# DDS.net
KiCad netlist of a schematic drawn in Altium Designer
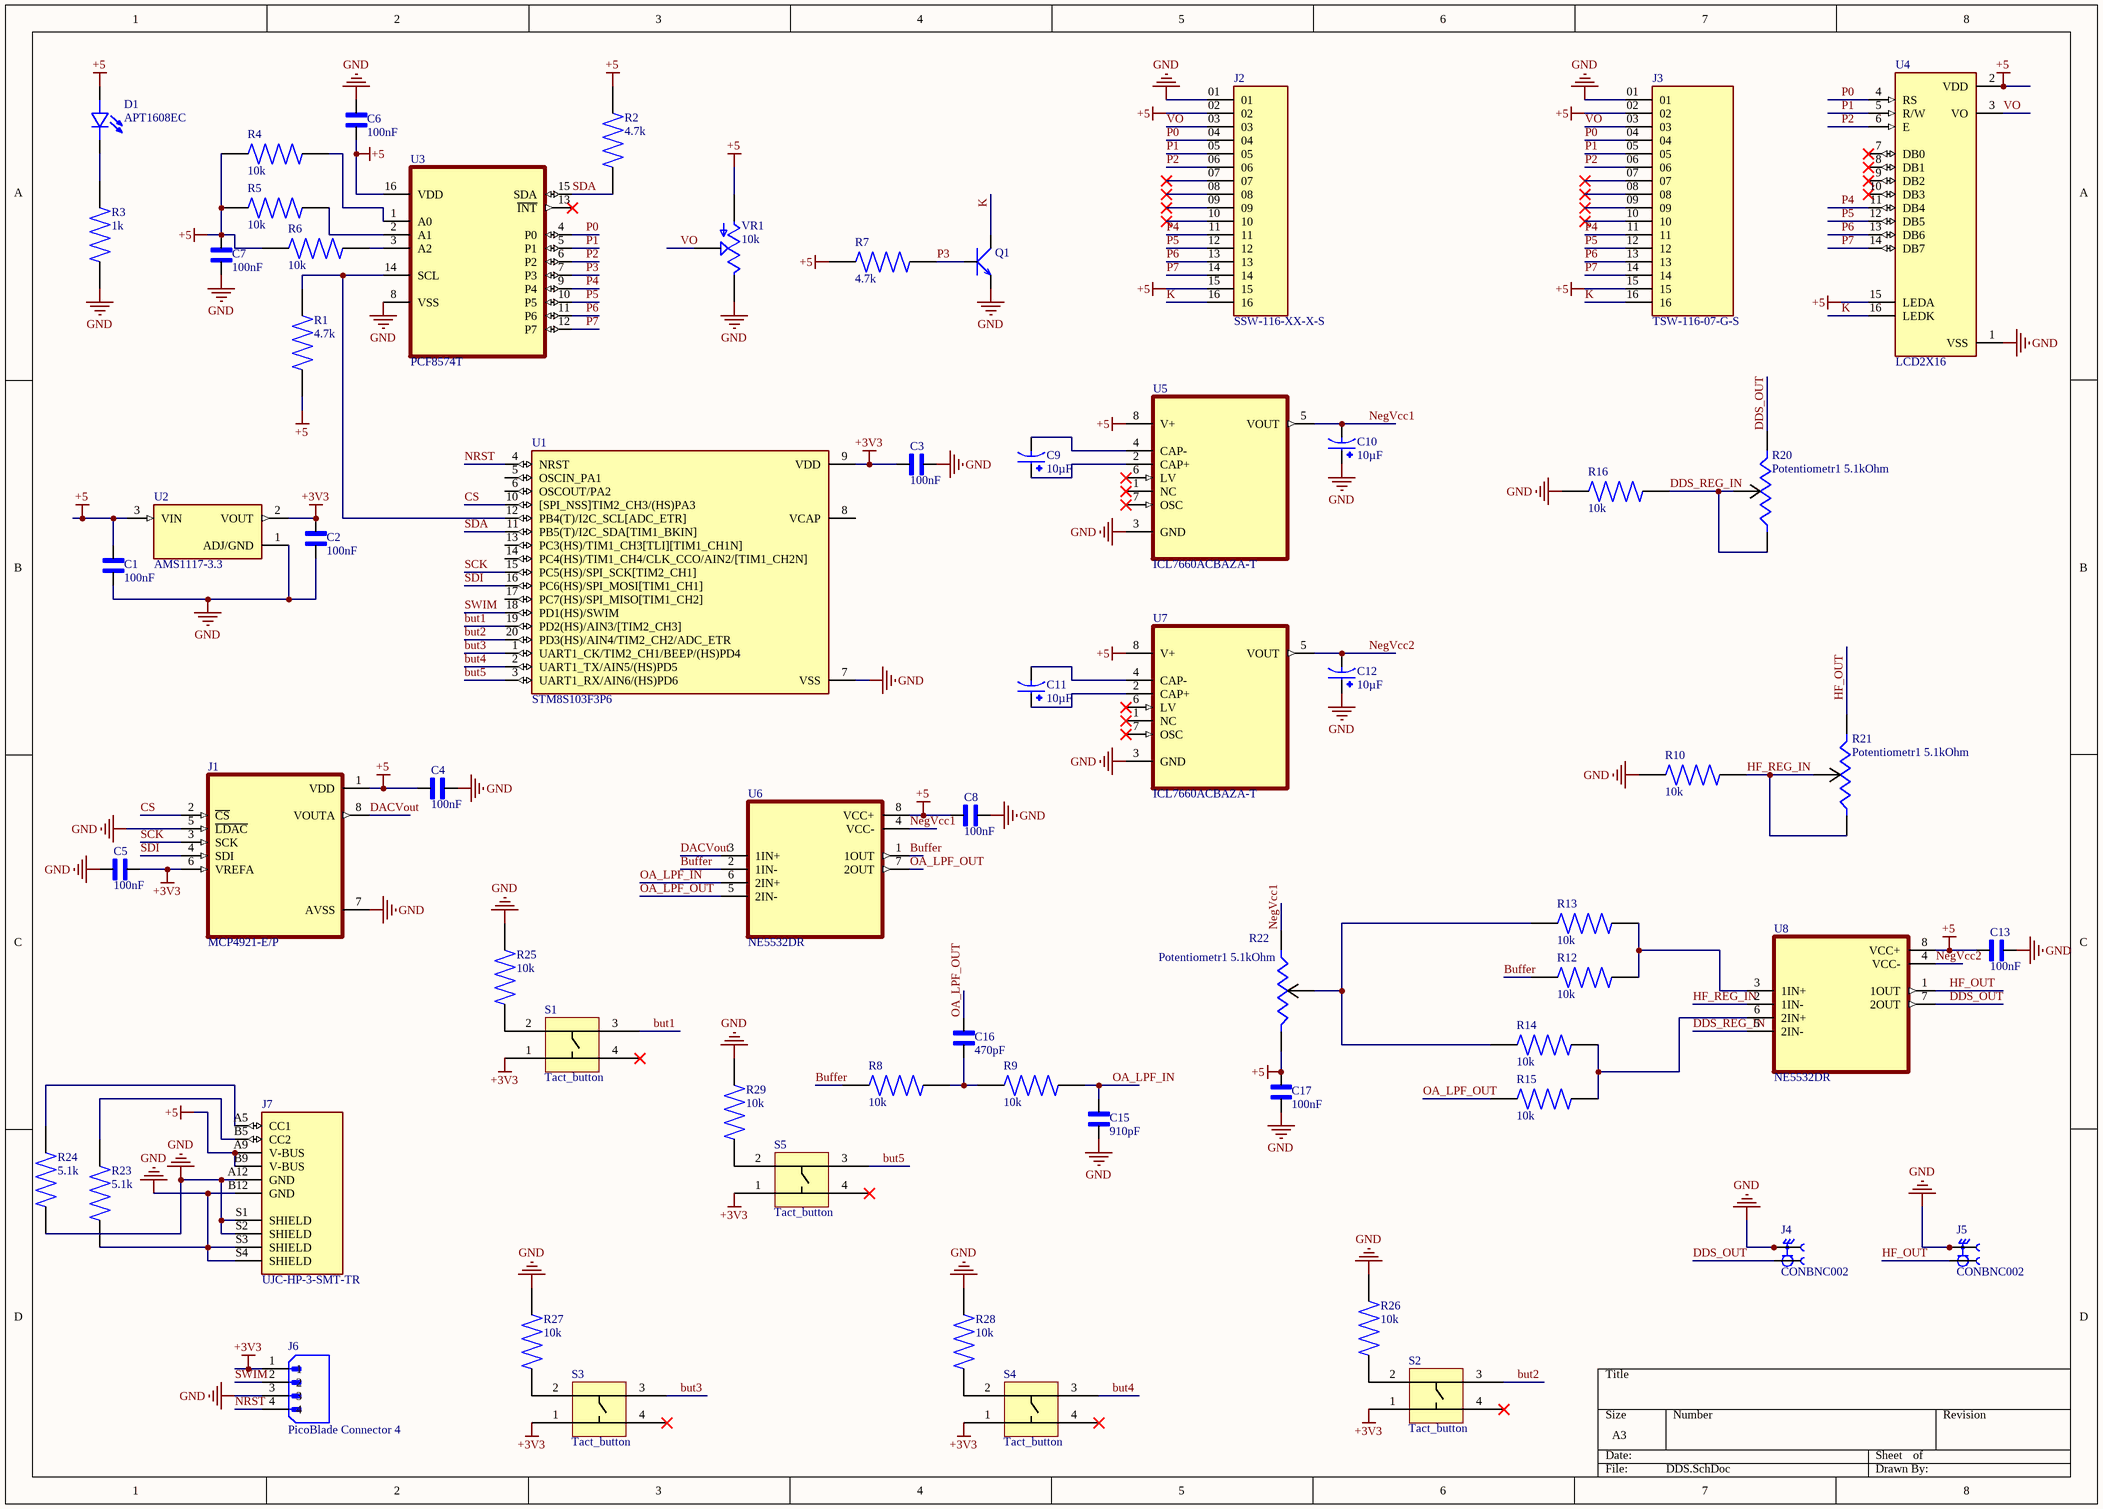
[diagram p0: DDS.SchDoc]

(export (version "E")
  (design (tool "Eeschema 10.0.6"))
  (components
    (comp (ref "C1")
      (value "100nF")
      (footprint "CAPC1608X90N")
      (description "0.1 ВµF В±10% 50V Ceramic Capacitor X7R 0603 (1608 Metric)")
      (fields (field (name "MF") "Samsung Electro-Mechanics") (field (name "MP") "CL10B104KB8NNNC"))
      (libsource (lib "") (part "CL10B104KB8NNNC_2"))
    )
    (comp (ref "C2")
      (value "100nF")
      (footprint "CAPC1608X90N")
      (description "0.1 ВµF В±10% 50V Ceramic Capacitor X7R 0603 (1608 Metric)")
      (fields (field (name "MF") "Samsung Electro-Mechanics") (field (name "MP") "CL10B104KB8NNNC"))
      (libsource (lib "") (part "CL10B104KB8NNNC_2"))
    )
    (comp (ref "C3")
      (value "100nF")
      (footprint "CAPC1608X90N")
      (description "0.1 ВµF В±10% 50V Ceramic Capacitor X7R 0603 (1608 Metric)")
      (fields (field (name "MF") "Samsung Electro-Mechanics") (field (name "MP") "CL10B104KB8NNNC"))
      (libsource (lib "") (part "CL10B104KB8NNNC_1"))
    )
    (comp (ref "C4")
      (value "100nF")
      (footprint "CAPC1608X90N")
      (description "0.1 ВµF В±10% 50V Ceramic Capacitor X7R 0603 (1608 Metric)")
      (fields (field (name "MF") "Samsung Electro-Mechanics") (field (name "MP") "CL10B104KB8NNNC"))
      (libsource (lib "") (part "CL10B104KB8NNNC_1"))
    )
    (comp (ref "C5")
      (value "100nF")
      (footprint "CAPC1608X90N")
      (description "0.1 ВµF В±10% 50V Ceramic Capacitor X7R 0603 (1608 Metric)")
      (fields (field (name "MF") "Samsung Electro-Mechanics") (field (name "MP") "CL10B104KB8NNNC"))
      (libsource (lib "National Technical University of Ukraine Igor Sikorsky Kyiv Polytechnic Institute- Educator Program") (part "CL10B104KB8NNNC"))
    )
    (comp (ref "C6")
      (value "100nF")
      (footprint "CAPC1608X90N")
      (description "0.1 ВµF В±10% 50V Ceramic Capacitor X7R 0603 (1608 Metric)")
      (fields (field (name "MF") "Samsung Electro-Mechanics") (field (name "MP") "CL10B104KB8NNNC"))
      (libsource (lib "") (part "CL10B104KB8NNNC_3"))
    )
    (comp (ref "C7")
      (value "100nF")
      (footprint "CAPC1608X90N")
      (description "0.1 ВµF В±10% 50V Ceramic Capacitor X7R 0603 (1608 Metric)")
      (fields (field (name "MF") "Samsung Electro-Mechanics") (field (name "MP") "CL10B104KB8NNNC"))
      (libsource (lib "") (part "CL10B104KB8NNNC_2"))
    )
    (comp (ref "C8")
      (value "100nF")
      (footprint "CAPC1608X90N")
      (description "0.1 ВµF В±10% 50V Ceramic Capacitor X7R 0603 (1608 Metric)")
      (fields (field (name "MF") "Samsung Electro-Mechanics") (field (name "MP") "CL10B104KB8NNNC"))
      (libsource (lib "") (part "CL10B104KB8NNNC_1"))
    )
    (comp (ref "C9")
      (value "10µF")
      (footprint "CAPPRD150W45D400H700")
      (description "10F 25V Aluminum Electrolytic Capacitors Radial, Can 1000 Hrs @ 105C")
      (fields (field (name "MP") "EEAFC1E100") (field (name "MF") "Panasonic"))
      (libsource (lib "National Technical University of Ukraine Igor Sikorsky Kyiv Polytechnic Institute- Educator Program") (part "EEAFC1E100"))
    )
    (comp (ref "C10")
      (value "10µF")
      (footprint "CAPPRD150W45D400H700")
      (description "10F 25V Aluminum Electrolytic Capacitors Radial, Can 1000 Hrs @ 105C")
      (fields (field (name "MP") "EEAFC1E100") (field (name "MF") "Panasonic"))
      (libsource (lib "National Technical University of Ukraine Igor Sikorsky Kyiv Polytechnic Institute- Educator Program") (part "EEAFC1E100"))
    )
    (comp (ref "C11")
      (value "10µF")
      (footprint "CAPPRD150W45D400H700")
      (description "10F 25V Aluminum Electrolytic Capacitors Radial, Can 1000 Hrs @ 105C")
      (fields (field (name "MP") "EEAFC1E100") (field (name "MF") "Panasonic"))
      (libsource (lib "National Technical University of Ukraine Igor Sikorsky Kyiv Polytechnic Institute- Educator Program") (part "EEAFC1E100"))
    )
    (comp (ref "C12")
      (value "10µF")
      (footprint "CAPPRD150W45D400H700")
      (description "10F 25V Aluminum Electrolytic Capacitors Radial, Can 1000 Hrs @ 105C")
      (fields (field (name "MP") "EEAFC1E100") (field (name "MF") "Panasonic"))
      (libsource (lib "National Technical University of Ukraine Igor Sikorsky Kyiv Polytechnic Institute- Educator Program") (part "EEAFC1E100"))
    )
    (comp (ref "C13")
      (value "100nF")
      (footprint "CAPC1608X90N")
      (description "0.1 ВµF В±10% 50V Ceramic Capacitor X7R 0603 (1608 Metric)")
      (fields (field (name "MF") "Samsung Electro-Mechanics") (field (name "MP") "CL10B104KB8NNNC"))
      (libsource (lib "") (part "CL10B104KB8NNNC_1"))
    )
    (comp (ref "C15")
      (value "910pF")
      (footprint "CAPC0603X33N")
      (fields (field (name "MF") "Murata") (field (name "MP") "GRM0335C1E911JA01D"))
      (libsource (lib "National Technical University of Ukraine Igor Sikorsky Kyiv Polytechnic Institute- Educator Program") (part "GRM0335C1E911JA01D"))
    )
    (comp (ref "C16")
      (value "470pF")
      (footprint "CAPC1608X90N")
      (description "470 pF В±5% 50V Ceramic Capacitor C0G, NP0 0603 (1608 Metric)")
      (fields (field (name "MF") "Samsung") (field (name "MP") "CL10C471JB8NNNC"))
      (libsource (lib "National Technical University of Ukraine Igor Sikorsky Kyiv Polytechnic Institute- Educator Program") (part "CL10C471JB8NNNC"))
    )
    (comp (ref "C17")
      (value "100nF")
      (footprint "CAPC1608X90N")
      (description "0.1 ВµF В±10% 50V Ceramic Capacitor X7R 0603 (1608 Metric)")
      (fields (field (name "MF") "Samsung Electro-Mechanics") (field (name "MP") "CL10B104KB8NNNC"))
      (libsource (lib "") (part "CL10B104KB8NNNC_2"))
    )
    (comp (ref "D1")
      (value "APT1608EC")
      (footprint "LED_APT1608EC")
      (description "Red 617nm LED Indication - Discrete 2V 0603 (1608 Metric)")
      (fields (field (name "MF") "Kingbright"))
      (libsource (lib "National Technical University of Ukraine Igor Sikorsky Kyiv Polytechnic Institute- Educator Program") (part "APT1608EC"))
    )
    (comp (ref "J1")
      (value "MCP4921-E/P")
      (footprint "DIP787W46P254L927H533Q8")
      (description "Microchip 12 bit Serial DAC 8-Pin PDIP")
      (fields (field (name "MF") "Microchip"))
      (libsource (lib "National Technical University of Ukraine Igor Sikorsky Kyiv Polytechnic Institute- Educator Program") (part "MCP4921-E/P"))
    )
    (comp (ref "J2")
      (value "SSW-116-XX-X-S")
      (footprint "SAMTEC_SSW-116-XX-X-S")
      (description "Conn Socket Strip SKT 16 POS 2.54mm Solder ST Top Entry Thru-Hole Bulk")
      (fields (field (name "MP") "SSW-116-06-G-S") (field (name "MF") "Samtec"))
      (libsource (lib "National Technical University of Ukraine Igor Sikorsky Kyiv Polytechnic Institute- Educator Program") (part "SSW-116-XX-X-S"))
    )
    (comp (ref "J3")
      (value "TSW-116-07-G-S")
      (footprint "SAMTEC_TSW-116-07-G-S")
      (fields (field (name "MF") "Samtec"))
      (libsource (lib "National Technical University of Ukraine Igor Sikorsky Kyiv Polytechnic Institute- Educator Program") (part "TSW-116-07-G-S"))
    )
    (comp (ref "J4")
      (value "CONBNC002")
      (footprint "LINX_CONBNC002")
      (description "BNC Jack 50 Ohm PCB Through Hole")
      (fields (field (name "MF") "Linx Technologies Inc."))
      (libsource (lib "National Technical University of Ukraine Igor Sikorsky Kyiv Polytechnic Institute- Educator Program") (part "CONBNC002"))
    )
    (comp (ref "J5")
      (value "CONBNC002")
      (footprint "LINX_CONBNC002")
      (description "BNC Jack 50 Ohm PCB Through Hole")
      (fields (field (name "MF") "Linx Technologies Inc."))
      (libsource (lib "National Technical University of Ukraine Igor Sikorsky Kyiv Polytechnic Institute- Educator Program") (part "CONBNC002"))
    )
    (comp (ref "J6")
      (value "PicoBlade Connector 4")
      (footprint "MOLEX_530470410")
      (description "Connector Header Through Hole 4 position 0.049 (1.25mm)")
      (fields (field (name "MF") "Molex") (field (name "MP") "530470410"))
      (libsource (lib "National Technical University of Ukraine Igor Sikorsky Kyiv Polytechnic Institute- Educator Program") (part "530470410"))
    )
    (comp (ref "J7")
      (value "UJC-HP-3-SMT-TR")
      (footprint "CUI_UJC-HP-3-SMT-TR")
      (libsource (lib "National Technical University of Ukraine Igor Sikorsky Kyiv Polytechnic Institute- Educator Program") (part "UJC-HP-3-SMT-TR"))
    )
    (comp (ref "Q1")
      (value "SMD-TRANSISTORS-NPN-25V-500MW(SOT-23)")
      (footprint "SOT-23")
      (description "Bipolar (BJT) Transistor NPN 25 V 500 mA 150MHz 300 mW Surface Mount SOT-23")
      (fields (field (name "MF") "UMW") (field (name "MP") "S8050"))
      (libsource (lib "National Technical University of Ukraine Igor Sikorsky Kyiv Polytechnic Institute- Educator Program") (part "SMD-TRANSISTORS-NPN-25V-500MW(SOT-23)"))
    )
    (comp (ref "R1")
      (value "4.7k")
      (footprint "RESC1608X55N")
      (description "Res Thick Film 0603 4.7K Ohm 1% 0.2W(1/5W) В±200ppm/C Pad SMD Automotive T/R")
      (fields (field (name "MF") "Panasonic") (field (name "MP") "ERJ-P03F4701V"))
      (libsource (lib "National Technical University of Ukraine Igor Sikorsky Kyiv Polytechnic Institute- Educator Program") (part "ERJ-P03F4701V"))
    )
    (comp (ref "R2")
      (value "4.7k")
      (footprint "RESC1608X55N")
      (description "Res Thick Film 0603 4.7K Ohm 1% 0.2W(1/5W) В±200ppm/C Pad SMD Automotive T/R")
      (fields (field (name "MF") "Panasonic") (field (name "MP") "ERJ-P03F4701V"))
      (libsource (lib "National Technical University of Ukraine Igor Sikorsky Kyiv Polytechnic Institute- Educator Program") (part "ERJ-P03F4701V"))
    )
    (comp (ref "R3")
      (value "1k")
      (footprint "RES_ERJP03F1001V")
      (description "Thick Film Smnt Resistor 0603 Case 1kOhm +/-1% 0.2W +/-200ppm/degC")
      (fields (field (name "MP") "ERJP03F1001V") (field (name "MF") "Panasonic"))
      (libsource (lib "National Technical University of Ukraine Igor Sikorsky Kyiv Polytechnic Institute- Educator Program") (part "ERJP03F1001V"))
    )
    (comp (ref "R4")
      (value "10k")
      (footprint "RES_ERJPA3F1002V")
      (fields
        (field (name "MP") "ERJ-PA3F1002V")
        (field (name "MF") "Panasonic")
        (field (name "Comment") "ERJPA3F1002V")
      )
      (libsource (lib "National Technical University of Ukraine Igor Sikorsky Kyiv Polytechnic Institute- Educator Program") (part "ERJPA3F1002V"))
    )
    (comp (ref "R5")
      (value "10k")
      (footprint "RES_ERJPA3F1002V")
      (fields
        (field (name "MP") "ERJ-PA3F1002V")
        (field (name "MF") "Panasonic")
        (field (name "Comment") "ERJPA3F1002V")
      )
      (libsource (lib "National Technical University of Ukraine Igor Sikorsky Kyiv Polytechnic Institute- Educator Program") (part "ERJPA3F1002V"))
    )
    (comp (ref "R6")
      (value "10k")
      (footprint "RES_ERJPA3F1002V")
      (fields
        (field (name "MP") "ERJ-PA3F1002V")
        (field (name "MF") "Panasonic")
        (field (name "Comment") "ERJPA3F1002V")
      )
      (libsource (lib "National Technical University of Ukraine Igor Sikorsky Kyiv Polytechnic Institute- Educator Program") (part "ERJPA3F1002V"))
    )
    (comp (ref "R7")
      (value "4.7k")
      (footprint "RESC1608X55N")
      (description "Res Thick Film 0603 4.7K Ohm 1% 0.2W(1/5W) В±200ppm/C Pad SMD Automotive T/R")
      (fields (field (name "MF") "Panasonic") (field (name "MP") "ERJ-P03F4701V"))
      (libsource (lib "National Technical University of Ukraine Igor Sikorsky Kyiv Polytechnic Institute- Educator Program") (part "ERJ-P03F4701V"))
    )
    (comp (ref "R8")
      (value "10k")
      (footprint "RES_ERJPA3F1002V")
      (fields
        (field (name "MP") "ERJ-PA3F1002V")
        (field (name "MF") "Panasonic")
        (field (name "Comment") "ERJPA3F1002V")
      )
      (libsource (lib "National Technical University of Ukraine Igor Sikorsky Kyiv Polytechnic Institute- Educator Program") (part "ERJPA3F1002V"))
    )
    (comp (ref "R9")
      (value "10k")
      (footprint "RES_ERJPA3F1002V")
      (fields
        (field (name "MP") "ERJ-PA3F1002V")
        (field (name "MF") "Panasonic")
        (field (name "Comment") "ERJPA3F1002V")
      )
      (libsource (lib "National Technical University of Ukraine Igor Sikorsky Kyiv Polytechnic Institute- Educator Program") (part "ERJPA3F1002V"))
    )
    (comp (ref "R10")
      (value "10k")
      (footprint "RES_ERJPA3F1002V")
      (fields
        (field (name "MP") "ERJ-PA3F1002V")
        (field (name "MF") "Panasonic")
        (field (name "Comment") "ERJPA3F1002V")
      )
      (libsource (lib "National Technical University of Ukraine Igor Sikorsky Kyiv Polytechnic Institute- Educator Program") (part "ERJPA3F1002V"))
    )
    (comp (ref "R12")
      (value "10k")
      (footprint "RES_ERJPA3F1002V")
      (fields
        (field (name "MP") "ERJ-PA3F1002V")
        (field (name "MF") "Panasonic")
        (field (name "Comment") "ERJPA3F1002V")
      )
      (libsource (lib "National Technical University of Ukraine Igor Sikorsky Kyiv Polytechnic Institute- Educator Program") (part "ERJPA3F1002V"))
    )
    (comp (ref "R13")
      (value "10k")
      (footprint "RES_ERJPA3F1002V")
      (fields
        (field (name "MP") "ERJ-PA3F1002V")
        (field (name "MF") "Panasonic")
        (field (name "Comment") "ERJPA3F1002V")
      )
      (libsource (lib "National Technical University of Ukraine Igor Sikorsky Kyiv Polytechnic Institute- Educator Program") (part "ERJPA3F1002V"))
    )
    (comp (ref "R14")
      (value "10k")
      (footprint "RES_ERJPA3F1002V")
      (fields
        (field (name "MP") "ERJ-PA3F1002V")
        (field (name "MF") "Panasonic")
        (field (name "Comment") "ERJPA3F1002V")
      )
      (libsource (lib "National Technical University of Ukraine Igor Sikorsky Kyiv Polytechnic Institute- Educator Program") (part "ERJPA3F1002V"))
    )
    (comp (ref "R15")
      (value "10k")
      (footprint "RES_ERJPA3F1002V")
      (fields
        (field (name "MP") "ERJ-PA3F1002V")
        (field (name "MF") "Panasonic")
        (field (name "Comment") "ERJPA3F1002V")
      )
      (libsource (lib "National Technical University of Ukraine Igor Sikorsky Kyiv Polytechnic Institute- Educator Program") (part "ERJPA3F1002V"))
    )
    (comp (ref "R16")
      (value "10k")
      (footprint "RES_ERJPA3F1002V")
      (fields
        (field (name "MP") "ERJ-PA3F1002V")
        (field (name "MF") "Panasonic")
        (field (name "Comment") "ERJPA3F1002V")
      )
      (libsource (lib "National Technical University of Ukraine Igor Sikorsky Kyiv Polytechnic Institute- Educator Program") (part "ERJPA3F1002V"))
    )
    (comp (ref "R20")
      (value "Potentiometr1 5.1kOhm")
      (footprint "PcbLib1:PotentiomenerFootprint")
      (libsource (lib "Schlib1") (part "Potentiometr1"))
    )
    (comp (ref "R21")
      (value "Potentiometr1 5.1kOhm")
      (footprint "PcbLib1:PotentiomenerFootprint")
      (libsource (lib "Schlib1") (part "Potentiometr1"))
    )
    (comp (ref "R22")
      (value "Potentiometr1 5.1kOhm")
      (footprint "PcbLib1:PotentiomenerFootprint")
      (libsource (lib "Schlib1") (part "Potentiometr1"))
    )
    (comp (ref "R23")
      (value "5.1k")
      (footprint "RES_ERJPA3F5101V")
      (description "Thick Film Smnt Resistor 0603 Case 5.1kOhm +/-1% 0.25W +/-100ppm/degC")
      (fields (field (name "MF") "Panasonic") (field (name "MP") "ERJPA3F5101V"))
      (libsource (lib "National Technical University of Ukraine Igor Sikorsky Kyiv Polytechnic Institute- Educator Program") (part "ERJPA3F5101V"))
    )
    (comp (ref "R24")
      (value "5.1k")
      (footprint "RES_ERJPA3F5101V")
      (description "Thick Film Smnt Resistor 0603 Case 5.1kOhm +/-1% 0.25W +/-100ppm/degC")
      (fields (field (name "MF") "Panasonic") (field (name "MP") "ERJPA3F5101V"))
      (libsource (lib "National Technical University of Ukraine Igor Sikorsky Kyiv Polytechnic Institute- Educator Program") (part "ERJPA3F5101V"))
    )
    (comp (ref "R25")
      (value "10k")
      (footprint "RES_ERJPA3F1002V")
      (fields
        (field (name "MP") "ERJ-PA3F1002V")
        (field (name "MF") "Panasonic")
        (field (name "Comment") "ERJPA3F1002V")
      )
      (libsource (lib "National Technical University of Ukraine Igor Sikorsky Kyiv Polytechnic Institute- Educator Program") (part "ERJPA3F1002V"))
    )
    (comp (ref "R26")
      (value "10k")
      (footprint "RES_ERJPA3F1002V")
      (fields
        (field (name "MP") "ERJ-PA3F1002V")
        (field (name "MF") "Panasonic")
        (field (name "Comment") "ERJPA3F1002V")
      )
      (libsource (lib "National Technical University of Ukraine Igor Sikorsky Kyiv Polytechnic Institute- Educator Program") (part "ERJPA3F1002V"))
    )
    (comp (ref "R27")
      (value "10k")
      (footprint "RES_ERJPA3F1002V")
      (fields
        (field (name "MP") "ERJ-PA3F1002V")
        (field (name "MF") "Panasonic")
        (field (name "Comment") "ERJPA3F1002V")
      )
      (libsource (lib "National Technical University of Ukraine Igor Sikorsky Kyiv Polytechnic Institute- Educator Program") (part "ERJPA3F1002V"))
    )
    (comp (ref "R28")
      (value "10k")
      (footprint "RES_ERJPA3F1002V")
      (fields
        (field (name "MP") "ERJ-PA3F1002V")
        (field (name "MF") "Panasonic")
        (field (name "Comment") "ERJPA3F1002V")
      )
      (libsource (lib "National Technical University of Ukraine Igor Sikorsky Kyiv Polytechnic Institute- Educator Program") (part "ERJPA3F1002V"))
    )
    (comp (ref "R29")
      (value "10k")
      (footprint "RES_ERJPA3F1002V")
      (fields
        (field (name "MP") "ERJ-PA3F1002V")
        (field (name "MF") "Panasonic")
        (field (name "Comment") "ERJPA3F1002V")
      )
      (libsource (lib "National Technical University of Ukraine Igor Sikorsky Kyiv Polytechnic Institute- Educator Program") (part "ERJPA3F1002V"))
    )
    (comp (ref "S1")
      (value "Tact_button")
      (footprint "TactButtonFootprint")
      (libsource (lib "Schlib1") (part "Tact_button"))
    )
    (comp (ref "S2")
      (value "Tact_button")
      (footprint "TactButtonFootprint")
      (libsource (lib "Schlib1") (part "Tact_button"))
    )
    (comp (ref "S3")
      (value "Tact_button")
      (footprint "TactButtonFootprint")
      (libsource (lib "Schlib1") (part "Tact_button"))
    )
    (comp (ref "S4")
      (value "Tact_button")
      (footprint "TactButtonFootprint")
      (libsource (lib "Schlib1") (part "Tact_button"))
    )
    (comp (ref "S5")
      (value "Tact_button")
      (footprint "TactButtonFootprint")
      (libsource (lib "Schlib1") (part "Tact_button"))
    )
    (comp (ref "U1")
      (value "STM8S103F3P6")
      (footprint "SOP65P640X120-20N")
      (description "STM8 series Microcontroller IC 8-Bit 16MHz 8KB (8K x 8) FLASH 20-TSSOP")
      (fields (field (name "MF") "STMicroelectronics"))
      (libsource (lib "National Technical University of Ukraine Igor Sikorsky Kyiv Polytechnic Institute- Educator Program") (part "STM8S103F3P6"))
    )
    (comp (ref "U2")
      (value "AMS1117-3.3")
      (footprint "SOT229P700X180-4N")
      (description "Linear Voltage Regulator IC Positive Fixed 1 Output 1A SOT-223-3L")
      (fields (field (name "MF") "UMW"))
      (libsource (lib "National Technical University of Ukraine Igor Sikorsky Kyiv Polytechnic Institute- Educator Program") (part "AMS1117-3.3"))
    )
    (comp (ref "U3")
      (value "PCF8574T")
      (footprint "SOIC127P1032X265-16N")
      (description "I/O Expander 8 IВІC 100 kHz 20-SSOP")
      (fields (field (name "MF") "NXP Semiconductors"))
      (libsource (lib "National Technical University of Ukraine Igor Sikorsky Kyiv Polytechnic Institute- Educator Program") (part "PCF8574T"))
    )
    (comp (ref "U4")
      (value "LCD2X16")
      (footprint "LCD_LCD2X16")
      (description "Display; Display: LCD 2x16 characters (blue backlight)")
      (fields (field (name "MF") "mikroElektronika") (field (name "MP") "LCD 2X16"))
      (libsource (lib "National Technical University of Ukraine Igor Sikorsky Kyiv Polytechnic Institute- Educator Program") (part "LCD2X16"))
    )
    (comp (ref "U5")
      (value "ICL7660ACBAZA-T")
      (footprint "SOIC127P600X175-8N")
      (fields (field (name "MF") "Renesas Electronics America Inc"))
      (libsource (lib "National Technical University of Ukraine Igor Sikorsky Kyiv Polytechnic Institute- Educator Program") (part "ICL7660ACBAZA-T"))
    )
    (comp (ref "U6")
      (value "NE5532DR")
      (footprint "SOIC127P599X175-8N")
      (description "Dual, 30-V, 10-MHz, low-noise operational amplifier for audio applications")
      (fields (field (name "MF") "Texas Instruments"))
      (libsource (lib "National Technical University of Ukraine Igor Sikorsky Kyiv Polytechnic Institute- Educator Program") (part "NE5532DR"))
    )
    (comp (ref "U7")
      (value "ICL7660ACBAZA-T")
      (footprint "SOIC127P600X175-8N")
      (fields (field (name "MF") "Renesas Electronics America Inc"))
      (libsource (lib "National Technical University of Ukraine Igor Sikorsky Kyiv Polytechnic Institute- Educator Program") (part "ICL7660ACBAZA-T"))
    )
    (comp (ref "U8")
      (value "NE5532DR")
      (footprint "SOIC127P599X175-8N")
      (description "Dual, 30-V, 10-MHz, low-noise operational amplifier for audio applications")
      (fields (field (name "MF") "Texas Instruments"))
      (libsource (lib "National Technical University of Ukraine Igor Sikorsky Kyiv Polytechnic Institute- Educator Program") (part "NE5532DR"))
    )
    (comp (ref "VR1")
      (value "10k")
      (footprint "TRIM_3362P-1-103LF")
      (description "Trimmer, Cermet, Rest 10 Kilohms, PCB, 1 Turns, Pwr-Rtg 0.5 W, Tol 10%")
      (fields (field (name "MP") "3362P-1-103LF") (field (name "MF") "Bourns"))
      (libsource (lib "National Technical University of Ukraine Igor Sikorsky Kyiv Polytechnic Institute- Educator Program") (part "3362P-1-103LF"))
    )
  )
  (nets
    (net (code "1") (name "+3V3") (class "Default")
      (node (ref "C2") (pin "2") (pinfunction "2_2") (pintype "passive"))
      (node (ref "C3") (pin "2") (pinfunction "2_2") (pintype "passive"))
      (node (ref "C5") (pin "2") (pinfunction "2_2") (pintype "passive"))
      (node (ref "J1") (pin "6") (pinfunction "VREFA_6") (pintype "input"))
      (node (ref "J6") (pin "1") (pinfunction "1_1") (pintype "passive"))
      (node (ref "S1") (pin "1") (pinfunction "1_1") (pintype "passive"))
      (node (ref "S2") (pin "1") (pinfunction "1_1") (pintype "passive"))
      (node (ref "S3") (pin "1") (pinfunction "1_1") (pintype "passive"))
      (node (ref "S4") (pin "1") (pinfunction "1_1") (pintype "passive"))
      (node (ref "S5") (pin "1") (pinfunction "1_1") (pintype "passive"))
      (node (ref "U1") (pin "9") (pinfunction "VDD_9") (pintype "passive"))
      (node (ref "U2") (pin "2") (pinfunction "VOUT_2") (pintype "output"))
    )
    (net (code "2") (name "+5") (class "Default")
      (node (ref "C1") (pin "2") (pinfunction "2_2") (pintype "passive"))
      (node (ref "C13") (pin "2") (pinfunction "2_2") (pintype "passive"))
      (node (ref "C17") (pin "2") (pinfunction "2_2") (pintype "passive"))
      (node (ref "C4") (pin "2") (pinfunction "2_2") (pintype "passive"))
      (node (ref "C6") (pin "2") (pinfunction "2_2") (pintype "passive"))
      (node (ref "C7") (pin "2") (pinfunction "2_2") (pintype "passive"))
      (node (ref "C8") (pin "2") (pinfunction "2_2") (pintype "passive"))
      (node (ref "D1") (pin "2") (pinfunction "A_2") (pintype "passive"))
      (node (ref "J1") (pin "1") (pinfunction "VDD_1") (pintype "passive"))
      (node (ref "J2") (pin "02") (pinfunction "02_02") (pintype "passive"))
      (node (ref "J2") (pin "15") (pinfunction "15_15") (pintype "passive"))
      (node (ref "J3") (pin "02") (pinfunction "02_02") (pintype "passive"))
      (node (ref "J3") (pin "15") (pinfunction "15_15") (pintype "passive"))
      (node (ref "J7") (pin "A9") (pinfunction "V-BUS_A9") (pintype "power_in"))
      (node (ref "J7") (pin "B9") (pinfunction "V-BUS_B9") (pintype "power_in"))
      (node (ref "R1") (pin "2") (pinfunction "2_2") (pintype "passive"))
      (node (ref "R2") (pin "2") (pinfunction "2_2") (pintype "passive"))
      (node (ref "R22") (pin "1") (pinfunction "1_1") (pintype "passive"))
      (node (ref "R4") (pin "2") (pinfunction "2_2") (pintype "passive"))
      (node (ref "R5") (pin "2") (pinfunction "2_2") (pintype "passive"))
      (node (ref "R6") (pin "2") (pinfunction "2_2") (pintype "passive"))
      (node (ref "R7") (pin "1") (pinfunction "1_1") (pintype "passive"))
      (node (ref "U2") (pin "3") (pinfunction "VIN_3") (pintype "input"))
      (node (ref "U3") (pin "16") (pinfunction "VDD_16") (pintype "power_in"))
      (node (ref "U4") (pin "15") (pinfunction "LEDA_15") (pintype "passive"))
      (node (ref "U4") (pin "2") (pinfunction "VDD_2") (pintype "passive"))
      (node (ref "U5") (pin "8") (pinfunction "V+_8") (pintype "power_in"))
      (node (ref "U6") (pin "8") (pinfunction "VCC+_8") (pintype "power_in"))
      (node (ref "U7") (pin "8") (pinfunction "V+_8") (pintype "power_in"))
      (node (ref "U8") (pin "8") (pinfunction "VCC+_8") (pintype "power_in"))
      (node (ref "VR1") (pin "1") (pinfunction "CCW_1") (pintype "passive"))
    )
    (net (code "3") (name "/Buffer") (class "Default")
      (node (ref "R12") (pin "2") (pinfunction "2_2") (pintype "passive"))
      (node (ref "R8") (pin "1") (pinfunction "1_1") (pintype "passive"))
      (node (ref "U6") (pin "1") (pinfunction "1OUT_1") (pintype "output"))
      (node (ref "U6") (pin "2") (pinfunction "1IN-_2") (pintype "passive"))
    )
    (net (code "4") (name "/CS") (class "Default")
      (node (ref "J1") (pin "2") (pinfunction "~{CS}_2") (pintype "input"))
      (node (ref "U1") (pin "10") (pinfunction "[SPI_NSS]TIM2_CH3/(HS)PA3_10") (pintype "bidirectional"))
    )
    (net (code "5") (name "/DACVout") (class "Default")
      (node (ref "J1") (pin "8") (pinfunction "VOUTA_8") (pintype "output"))
      (node (ref "U6") (pin "3") (pinfunction "1IN+_3") (pintype "passive"))
    )
    (net (code "6") (name "/DDS_OUT") (class "Default")
      (node (ref "J4") (pin "1") (pinfunction "1_1") (pintype "passive"))
      (node (ref "R20") (pin "1") (pinfunction "1_1") (pintype "passive"))
      (node (ref "U8") (pin "7") (pinfunction "2OUT_7") (pintype "output"))
    )
    (net (code "7") (name "/DDS_REG_IN") (class "Default")
      (node (ref "R16") (pin "2") (pinfunction "2_2") (pintype "passive"))
      (node (ref "R20") (pin "2") (pinfunction "2_2") (pintype "passive"))
      (node (ref "R20") (pin "3") (pinfunction "3_3") (pintype "passive"))
      (node (ref "U8") (pin "5") (pinfunction "2IN-_5") (pintype "passive"))
    )
    (net (code "8") (name "/HF_OUT") (class "Default")
      (node (ref "J5") (pin "1") (pinfunction "1_1") (pintype "passive"))
      (node (ref "R21") (pin "1") (pinfunction "1_1") (pintype "passive"))
      (node (ref "U8") (pin "1") (pinfunction "1OUT_1") (pintype "output"))
    )
    (net (code "9") (name "/HF_REG_IN") (class "Default")
      (node (ref "R10") (pin "2") (pinfunction "2_2") (pintype "passive"))
      (node (ref "R21") (pin "2") (pinfunction "2_2") (pintype "passive"))
      (node (ref "R21") (pin "3") (pinfunction "3_3") (pintype "passive"))
      (node (ref "U8") (pin "2") (pinfunction "1IN-_2") (pintype "passive"))
    )
    (net (code "10") (name "/K") (class "Default")
      (node (ref "J2") (pin "16") (pinfunction "16_16") (pintype "passive"))
      (node (ref "J3") (pin "16") (pinfunction "16_16") (pintype "passive"))
      (node (ref "Q1") (pin "3") (pinfunction "C_3") (pintype "passive"))
      (node (ref "U4") (pin "16") (pinfunction "LEDK_16") (pintype "passive"))
    )
    (net (code "11") (name "/NRST") (class "Default")
      (node (ref "J6") (pin "4") (pinfunction "4_4") (pintype "passive"))
      (node (ref "U1") (pin "4") (pinfunction "NRST_4") (pintype "bidirectional"))
    )
    (net (code "12") (name "/NegVcc1") (class "Default")
      (node (ref "C10") (pin "N") (pinfunction "N_N") (pintype "passive"))
      (node (ref "R22") (pin "3") (pinfunction "3_3") (pintype "passive"))
      (node (ref "U5") (pin "5") (pinfunction "VOUT_5") (pintype "output"))
      (node (ref "U6") (pin "4") (pinfunction "VCC-_4") (pintype "passive"))
    )
    (net (code "13") (name "/NegVcc2") (class "Default")
      (node (ref "C12") (pin "N") (pinfunction "N_N") (pintype "passive"))
      (node (ref "U7") (pin "5") (pinfunction "VOUT_5") (pintype "output"))
      (node (ref "U8") (pin "4") (pinfunction "VCC-_4") (pintype "passive"))
    )
    (net (code "14") (name "/OA_LPF_IN") (class "Default")
      (node (ref "C15") (pin "2") (pinfunction "2_2") (pintype "passive"))
      (node (ref "R9") (pin "1") (pinfunction "1_1") (pintype "passive"))
      (node (ref "U6") (pin "6") (pinfunction "2IN+_6") (pintype "passive"))
    )
    (net (code "15") (name "/OA_LPF_OUT") (class "Default")
      (node (ref "C16") (pin "2") (pinfunction "2_2") (pintype "passive"))
      (node (ref "R15") (pin "2") (pinfunction "2_2") (pintype "passive"))
      (node (ref "U6") (pin "5") (pinfunction "2IN-_5") (pintype "passive"))
      (node (ref "U6") (pin "7") (pinfunction "2OUT_7") (pintype "output"))
    )
    (net (code "16") (name "/P0") (class "Default")
      (node (ref "J2") (pin "04") (pinfunction "04_04") (pintype "passive"))
      (node (ref "J3") (pin "04") (pinfunction "04_04") (pintype "passive"))
      (node (ref "U3") (pin "4") (pinfunction "P0_4") (pintype "bidirectional"))
      (node (ref "U4") (pin "4") (pinfunction "RS_4") (pintype "input"))
    )
    (net (code "17") (name "/P1") (class "Default")
      (node (ref "J2") (pin "05") (pinfunction "05_05") (pintype "passive"))
      (node (ref "J3") (pin "05") (pinfunction "05_05") (pintype "passive"))
      (node (ref "U3") (pin "5") (pinfunction "P1_5") (pintype "bidirectional"))
      (node (ref "U4") (pin "5") (pinfunction "R/W_5") (pintype "input"))
    )
    (net (code "18") (name "/P2") (class "Default")
      (node (ref "J2") (pin "06") (pinfunction "06_06") (pintype "passive"))
      (node (ref "J3") (pin "06") (pinfunction "06_06") (pintype "passive"))
      (node (ref "U3") (pin "6") (pinfunction "P2_6") (pintype "bidirectional"))
      (node (ref "U4") (pin "6") (pinfunction "E_6") (pintype "input"))
    )
    (net (code "19") (name "/P3") (class "Default")
      (node (ref "Q1") (pin "1") (pinfunction "B_1") (pintype "passive"))
      (node (ref "R7") (pin "2") (pinfunction "2_2") (pintype "passive"))
      (node (ref "U3") (pin "7") (pinfunction "P3_7") (pintype "bidirectional"))
    )
    (net (code "20") (name "/P4") (class "Default")
      (node (ref "J2") (pin "11") (pinfunction "11_11") (pintype "passive"))
      (node (ref "J3") (pin "11") (pinfunction "11_11") (pintype "passive"))
      (node (ref "U3") (pin "9") (pinfunction "P4_9") (pintype "bidirectional"))
      (node (ref "U4") (pin "11") (pinfunction "DB4_11") (pintype "bidirectional"))
    )
    (net (code "21") (name "/P5") (class "Default")
      (node (ref "J2") (pin "12") (pinfunction "12_12") (pintype "passive"))
      (node (ref "J3") (pin "12") (pinfunction "12_12") (pintype "passive"))
      (node (ref "U3") (pin "10") (pinfunction "P5_10") (pintype "bidirectional"))
      (node (ref "U4") (pin "12") (pinfunction "DB5_12") (pintype "bidirectional"))
    )
    (net (code "22") (name "/P6") (class "Default")
      (node (ref "J2") (pin "13") (pinfunction "13_13") (pintype "passive"))
      (node (ref "J3") (pin "13") (pinfunction "13_13") (pintype "passive"))
      (node (ref "U3") (pin "11") (pinfunction "P6_11") (pintype "bidirectional"))
      (node (ref "U4") (pin "13") (pinfunction "DB6_13") (pintype "bidirectional"))
    )
    (net (code "23") (name "/P7") (class "Default")
      (node (ref "J2") (pin "14") (pinfunction "14_14") (pintype "passive"))
      (node (ref "J3") (pin "14") (pinfunction "14_14") (pintype "passive"))
      (node (ref "U3") (pin "12") (pinfunction "P7_12") (pintype "bidirectional"))
      (node (ref "U4") (pin "14") (pinfunction "DB7_14") (pintype "bidirectional"))
    )
    (net (code "24") (name "/SCK") (class "Default")
      (node (ref "J1") (pin "3") (pinfunction "SCK_3") (pintype "input"))
      (node (ref "U1") (pin "15") (pinfunction "PC5(HS)/SPI_SCK[TIM2_CH1]_15") (pintype "bidirectional"))
    )
    (net (code "25") (name "/SDA") (class "Default")
      (node (ref "R2") (pin "1") (pinfunction "1_1") (pintype "passive"))
      (node (ref "U1") (pin "11") (pinfunction "PB5(T)/I2C_SDA[TIM1_BKIN]_11") (pintype "bidirectional"))
      (node (ref "U3") (pin "15") (pinfunction "SDA_15") (pintype "bidirectional"))
    )
    (net (code "26") (name "/SDI") (class "Default")
      (node (ref "J1") (pin "4") (pinfunction "SDI_4") (pintype "input"))
      (node (ref "U1") (pin "16") (pinfunction "PC6(HS)/SPI_MOSI[TIM1_CH1]_16") (pintype "bidirectional"))
    )
    (net (code "27") (name "/SWIM") (class "Default")
      (node (ref "J6") (pin "2") (pinfunction "2_2") (pintype "passive"))
      (node (ref "U1") (pin "18") (pinfunction "PD1(HS)/SWIM_18") (pintype "bidirectional"))
    )
    (net (code "28") (name "/VO") (class "Default")
      (node (ref "J2") (pin "03") (pinfunction "03_03") (pintype "passive"))
      (node (ref "J3") (pin "03") (pinfunction "03_03") (pintype "passive"))
      (node (ref "U4") (pin "3") (pinfunction "VO_3") (pintype "passive"))
      (node (ref "VR1") (pin "2") (pinfunction "WIPER_2") (pintype "passive"))
    )
    (net (code "29") (name "/but1") (class "Default")
      (node (ref "S1") (pin "3") (pinfunction "3_3") (pintype "passive"))
      (node (ref "U1") (pin "19") (pinfunction "PD2(HS)/AIN3/[TIM2_CH3]_19") (pintype "bidirectional"))
    )
    (net (code "30") (name "/but2") (class "Default")
      (node (ref "S2") (pin "3") (pinfunction "3_3") (pintype "passive"))
      (node (ref "U1") (pin "20") (pinfunction "PD3(HS)/AIN4/TIM2_CH2/ADC_ETR_20") (pintype "bidirectional"))
    )
    (net (code "31") (name "/but3") (class "Default")
      (node (ref "S3") (pin "3") (pinfunction "3_3") (pintype "passive"))
      (node (ref "U1") (pin "1") (pinfunction "UART1_CK/TIM2_CH1/BEEP/(HS)PD4_1") (pintype "bidirectional"))
    )
    (net (code "32") (name "/but4") (class "Default")
      (node (ref "S4") (pin "3") (pinfunction "3_3") (pintype "passive"))
      (node (ref "U1") (pin "2") (pinfunction "UART1_TX/AIN5/(HS)PD5_2") (pintype "bidirectional"))
    )
    (net (code "33") (name "/but5") (class "Default")
      (node (ref "S5") (pin "3") (pinfunction "3_3") (pintype "passive"))
      (node (ref "U1") (pin "3") (pinfunction "UART1_RX/AIN6/(HS)PD6_3") (pintype "bidirectional"))
    )
    (net (code "34") (name "GND") (class "Default")
      (node (ref "C1") (pin "1") (pinfunction "1_1") (pintype "passive"))
      (node (ref "C10") (pin "P") (pinfunction "P_P") (pintype "passive"))
      (node (ref "C12") (pin "P") (pinfunction "P_P") (pintype "passive"))
      (node (ref "C13") (pin "1") (pinfunction "1_1") (pintype "passive"))
      (node (ref "C15") (pin "1") (pinfunction "1_1") (pintype "passive"))
      (node (ref "C17") (pin "1") (pinfunction "1_1") (pintype "passive"))
      (node (ref "C2") (pin "1") (pinfunction "1_1") (pintype "passive"))
      (node (ref "C3") (pin "1") (pinfunction "1_1") (pintype "passive"))
      (node (ref "C4") (pin "1") (pinfunction "1_1") (pintype "passive"))
      (node (ref "C5") (pin "1") (pinfunction "1_1") (pintype "passive"))
      (node (ref "C6") (pin "1") (pinfunction "1_1") (pintype "passive"))
      (node (ref "C7") (pin "1") (pinfunction "1_1") (pintype "passive"))
      (node (ref "C8") (pin "1") (pinfunction "1_1") (pintype "passive"))
      (node (ref "J1") (pin "5") (pinfunction "~{LDAC}_5") (pintype "input"))
      (node (ref "J1") (pin "7") (pinfunction "AVSS_7") (pintype "power_in"))
      (node (ref "J2") (pin "01") (pinfunction "01_01") (pintype "passive"))
      (node (ref "J3") (pin "01") (pinfunction "01_01") (pintype "passive"))
      (node (ref "J4") (pin "2") (pinfunction "2_2") (pintype "passive"))
      (node (ref "J4") (pin "S1") (pinfunction "2_S1") (pintype "passive"))
      (node (ref "J4") (pin "S2") (pinfunction "2_S2") (pintype "passive"))
      (node (ref "J5") (pin "2") (pinfunction "2_2") (pintype "passive"))
      (node (ref "J5") (pin "S1") (pinfunction "2_S1") (pintype "passive"))
      (node (ref "J5") (pin "S2") (pinfunction "2_S2") (pintype "passive"))
      (node (ref "J6") (pin "3") (pinfunction "3_3") (pintype "passive"))
      (node (ref "J7") (pin "A12") (pinfunction "GND_A12") (pintype "power_in"))
      (node (ref "J7") (pin "B12") (pinfunction "GND_B12") (pintype "power_in"))
      (node (ref "J7") (pin "S1") (pinfunction "SHIELD_S1") (pintype "passive"))
      (node (ref "J7") (pin "S2") (pinfunction "SHIELD_S2") (pintype "passive"))
      (node (ref "J7") (pin "S3") (pinfunction "SHIELD_S3") (pintype "passive"))
      (node (ref "J7") (pin "S4") (pinfunction "SHIELD_S4") (pintype "passive"))
      (node (ref "Q1") (pin "2") (pinfunction "E_2") (pintype "passive"))
      (node (ref "R10") (pin "1") (pinfunction "1_1") (pintype "passive"))
      (node (ref "R16") (pin "1") (pinfunction "1_1") (pintype "passive"))
      (node (ref "R23") (pin "1") (pinfunction "1_1") (pintype "passive"))
      (node (ref "R24") (pin "1") (pinfunction "1_1") (pintype "passive"))
      (node (ref "R25") (pin "2") (pinfunction "2_2") (pintype "passive"))
      (node (ref "R26") (pin "2") (pinfunction "2_2") (pintype "passive"))
      (node (ref "R27") (pin "2") (pinfunction "2_2") (pintype "passive"))
      (node (ref "R28") (pin "2") (pinfunction "2_2") (pintype "passive"))
      (node (ref "R29") (pin "2") (pinfunction "2_2") (pintype "passive"))
      (node (ref "R3") (pin "1") (pinfunction "1_1") (pintype "passive"))
      (node (ref "U1") (pin "7") (pinfunction "VSS_7") (pintype "power_in"))
      (node (ref "U2") (pin "1") (pinfunction "ADJ/GND_1") (pintype "power_in"))
      (node (ref "U3") (pin "8") (pinfunction "VSS_8") (pintype "passive"))
      (node (ref "U4") (pin "1") (pinfunction "VSS_1") (pintype "power_in"))
      (node (ref "U5") (pin "3") (pinfunction "GND_3") (pintype "passive"))
      (node (ref "U7") (pin "3") (pinfunction "GND_3") (pintype "passive"))
      (node (ref "VR1") (pin "3") (pinfunction "CW_3") (pintype "passive"))
    )
    (net (code "35") (name "Net-(C16-Pad1)") (class "Default")
      (node (ref "C16") (pin "1") (pinfunction "1_1") (pintype "passive"))
      (node (ref "R8") (pin "2") (pinfunction "2_2") (pintype "passive"))
      (node (ref "R9") (pin "2") (pinfunction "2_2") (pintype "passive"))
    )
    (net (code "36") (name "Net-(D1-C)") (class "Default")
      (node (ref "D1") (pin "1") (pinfunction "C_1") (pintype "passive"))
      (node (ref "R3") (pin "2") (pinfunction "2_2") (pintype "passive"))
    )
    (net (code "37") (name "Net-(J7-CC1)") (class "Default")
      (node (ref "J7") (pin "A5") (pinfunction "CC1_A5") (pintype "bidirectional"))
      (node (ref "R24") (pin "2") (pinfunction "2_2") (pintype "passive"))
    )
    (net (code "38") (name "Net-(J7-CC2)") (class "Default")
      (node (ref "J7") (pin "B5") (pinfunction "CC2_B5") (pintype "bidirectional"))
      (node (ref "R23") (pin "2") (pinfunction "2_2") (pintype "passive"))
    )
    (net (code "39") (name "Net-(R13-Pad2)") (class "Default")
      (node (ref "R13") (pin "2") (pinfunction "2_2") (pintype "passive"))
      (node (ref "R14") (pin "2") (pinfunction "2_2") (pintype "passive"))
      (node (ref "R22") (pin "2") (pinfunction "2_2") (pintype "passive"))
    )
    (net (code "40") (name "Net-(R25-Pad1)") (class "Default")
      (node (ref "R25") (pin "1") (pinfunction "1_1") (pintype "passive"))
      (node (ref "S1") (pin "2") (pinfunction "2_2") (pintype "passive"))
    )
    (net (code "41") (name "Net-(R26-Pad1)") (class "Default")
      (node (ref "R26") (pin "1") (pinfunction "1_1") (pintype "passive"))
      (node (ref "S2") (pin "2") (pinfunction "2_2") (pintype "passive"))
    )
    (net (code "42") (name "Net-(R27-Pad1)") (class "Default")
      (node (ref "R27") (pin "1") (pinfunction "1_1") (pintype "passive"))
      (node (ref "S3") (pin "2") (pinfunction "2_2") (pintype "passive"))
    )
    (net (code "43") (name "Net-(R28-Pad1)") (class "Default")
      (node (ref "R28") (pin "1") (pinfunction "1_1") (pintype "passive"))
      (node (ref "S4") (pin "2") (pinfunction "2_2") (pintype "passive"))
    )
    (net (code "44") (name "Net-(R29-Pad1)") (class "Default")
      (node (ref "R29") (pin "1") (pinfunction "1_1") (pintype "passive"))
      (node (ref "S5") (pin "2") (pinfunction "2_2") (pintype "passive"))
    )
    (net (code "45") (name "Net-(U1-PB4(T){slash}I2C_SCL[ADC_ETR])") (class "Default")
      (node (ref "R1") (pin "1") (pinfunction "1_1") (pintype "passive"))
      (node (ref "U1") (pin "12") (pinfunction "PB4(T)/I2C_SCL[ADC_ETR]_12") (pintype "bidirectional"))
      (node (ref "U3") (pin "14") (pinfunction "SCL_14") (pintype "passive"))
    )
    (net (code "46") (name "Net-(U3-A0)") (class "Default")
      (node (ref "R4") (pin "1") (pinfunction "1_1") (pintype "passive"))
      (node (ref "U3") (pin "1") (pinfunction "A0_1") (pintype "passive"))
    )
    (net (code "47") (name "Net-(U3-A1)") (class "Default")
      (node (ref "R5") (pin "1") (pinfunction "1_1") (pintype "passive"))
      (node (ref "U3") (pin "2") (pinfunction "A1_2") (pintype "passive"))
    )
    (net (code "48") (name "Net-(U3-A2)") (class "Default")
      (node (ref "R6") (pin "1") (pinfunction "1_1") (pintype "passive"))
      (node (ref "U3") (pin "3") (pinfunction "A2_3") (pintype "passive"))
    )
    (net (code "49") (name "Net-(U5-CAP+)") (class "Default")
      (node (ref "C9") (pin "P") (pinfunction "P_P") (pintype "passive"))
      (node (ref "U5") (pin "2") (pinfunction "CAP+_2") (pintype "passive"))
    )
    (net (code "50") (name "Net-(U5-CAP-)") (class "Default")
      (node (ref "C9") (pin "N") (pinfunction "N_N") (pintype "passive"))
      (node (ref "U5") (pin "4") (pinfunction "CAP-_4") (pintype "passive"))
    )
    (net (code "51") (name "Net-(U7-CAP+)") (class "Default")
      (node (ref "C11") (pin "P") (pinfunction "P_P") (pintype "passive"))
      (node (ref "U7") (pin "2") (pinfunction "CAP+_2") (pintype "passive"))
    )
    (net (code "52") (name "Net-(U7-CAP-)") (class "Default")
      (node (ref "C11") (pin "N") (pinfunction "N_N") (pintype "passive"))
      (node (ref "U7") (pin "4") (pinfunction "CAP-_4") (pintype "passive"))
    )
    (net (code "53") (name "Net-(U8-1IN+)") (class "Default")
      (node (ref "R12") (pin "1") (pinfunction "1_1") (pintype "passive"))
      (node (ref "R13") (pin "1") (pinfunction "1_1") (pintype "passive"))
      (node (ref "U8") (pin "3") (pinfunction "1IN+_3") (pintype "passive"))
    )
    (net (code "54") (name "Net-(U8-2IN+)") (class "Default")
      (node (ref "R14") (pin "1") (pinfunction "1_1") (pintype "passive"))
      (node (ref "R15") (pin "1") (pinfunction "1_1") (pintype "passive"))
      (node (ref "U8") (pin "6") (pinfunction "2IN+_6") (pintype "passive"))
    )
    (net (code "55") (name "unconnected-(J1-3-Pad0)") (class "Default")
      (node (ref "J1") (pin "0") (pinfunction "3_0") (pintype "passive"))
    )
    (net (code "56") (name "unconnected-(J2-Pad07)") (class "Default")
      (node (ref "J2") (pin "07") (pinfunction "07_07") (pintype "passive+no_connect"))
    )
    (net (code "57") (name "unconnected-(J2-Pad08)") (class "Default")
      (node (ref "J2") (pin "08") (pinfunction "08_08") (pintype "passive+no_connect"))
    )
    (net (code "58") (name "unconnected-(J2-Pad09)") (class "Default")
      (node (ref "J2") (pin "09") (pinfunction "09_09") (pintype "passive+no_connect"))
    )
    (net (code "59") (name "unconnected-(J2-Pad10)") (class "Default")
      (node (ref "J2") (pin "10") (pinfunction "10_10") (pintype "passive+no_connect"))
    )
    (net (code "60") (name "unconnected-(J3-Pad07)") (class "Default")
      (node (ref "J3") (pin "07") (pinfunction "07_07") (pintype "passive+no_connect"))
    )
    (net (code "61") (name "unconnected-(J3-Pad08)") (class "Default")
      (node (ref "J3") (pin "08") (pinfunction "08_08") (pintype "passive+no_connect"))
    )
    (net (code "62") (name "unconnected-(J3-Pad09)") (class "Default")
      (node (ref "J3") (pin "09") (pinfunction "09_09") (pintype "passive+no_connect"))
    )
    (net (code "63") (name "unconnected-(J3-Pad10)") (class "Default")
      (node (ref "J3") (pin "10") (pinfunction "10_10") (pintype "passive+no_connect"))
    )
    (net (code "64") (name "unconnected-(S1-Pad4)") (class "Default")
      (node (ref "S1") (pin "4") (pinfunction "4_4") (pintype "passive+no_connect"))
    )
    (net (code "65") (name "unconnected-(S2-Pad4)") (class "Default")
      (node (ref "S2") (pin "4") (pinfunction "4_4") (pintype "passive+no_connect"))
    )
    (net (code "66") (name "unconnected-(S3-Pad4)") (class "Default")
      (node (ref "S3") (pin "4") (pinfunction "4_4") (pintype "passive+no_connect"))
    )
    (net (code "67") (name "unconnected-(S4-Pad4)") (class "Default")
      (node (ref "S4") (pin "4") (pinfunction "4_4") (pintype "passive+no_connect"))
    )
    (net (code "68") (name "unconnected-(S5-Pad4)") (class "Default")
      (node (ref "S5") (pin "4") (pinfunction "4_4") (pintype "passive+no_connect"))
    )
    (net (code "69") (name "unconnected-(U1-OSCIN_PA1-Pad5)") (class "Default")
      (node (ref "U1") (pin "5") (pinfunction "OSCIN_PA1_5") (pintype "bidirectional"))
    )
    (net (code "70") (name "unconnected-(U1-OSCOUT{slash}PA2-Pad6)") (class "Default")
      (node (ref "U1") (pin "6") (pinfunction "OSCOUT/PA2_6") (pintype "bidirectional"))
    )
    (net (code "71") (name "unconnected-(U1-PC3(HS){slash}TIM1_CH3[TLI][TIM1_CH1N]-Pad13)") (class "Default")
      (node (ref "U1") (pin "13") (pinfunction "PC3(HS)/TIM1_CH3[TLI][TIM1_CH1N]_13") (pintype "bidirectional"))
    )
    (net (code "72") (name "unconnected-(U1-PC4(HS){slash}TIM1_CH4{slash}CLK_CCO{slash}AIN2{slash}[TIM1_CH2N]-Pad14)") (class "Default")
      (node (ref "U1") (pin "14") (pinfunction "PC4(HS)/TIM1_CH4/CLK_CCO/AIN2/[TIM1_CH2N]_14") (pintype "bidirectional"))
    )
    (net (code "73") (name "unconnected-(U1-PC7(HS){slash}SPI_MISO[TIM1_CH2]-Pad17)") (class "Default")
      (node (ref "U1") (pin "17") (pinfunction "PC7(HS)/SPI_MISO[TIM1_CH2]_17") (pintype "bidirectional"))
    )
    (net (code "74") (name "unconnected-(U1-VCAP-Pad8)") (class "Default")
      (node (ref "U1") (pin "8") (pinfunction "VCAP_8") (pintype "passive"))
    )
    (net (code "75") (name "unconnected-(U3-~{INT}-Pad13)") (class "Default")
      (node (ref "U3") (pin "13") (pinfunction "~{INT}_13") (pintype "output+no_connect"))
    )
    (net (code "76") (name "unconnected-(U4-DB0-Pad7)") (class "Default")
      (node (ref "U4") (pin "7") (pinfunction "DB0_7") (pintype "bidirectional+no_connect"))
    )
    (net (code "77") (name "unconnected-(U4-DB1-Pad8)") (class "Default")
      (node (ref "U4") (pin "8") (pinfunction "DB1_8") (pintype "bidirectional+no_connect"))
    )
    (net (code "78") (name "unconnected-(U4-DB2-Pad9)") (class "Default")
      (node (ref "U4") (pin "9") (pinfunction "DB2_9") (pintype "bidirectional+no_connect"))
    )
    (net (code "79") (name "unconnected-(U4-DB3-Pad10)") (class "Default")
      (node (ref "U4") (pin "10") (pinfunction "DB3_10") (pintype "bidirectional+no_connect"))
    )
    (net (code "80") (name "unconnected-(U5-LV-Pad6)") (class "Default")
      (node (ref "U5") (pin "6") (pinfunction "LV_6") (pintype "input+no_connect"))
    )
    (net (code "81") (name "unconnected-(U5-NC-Pad1)") (class "Default")
      (node (ref "U5") (pin "1") (pinfunction "NC_1") (pintype "passive+no_connect"))
    )
    (net (code "82") (name "unconnected-(U5-OSC-Pad7)") (class "Default")
      (node (ref "U5") (pin "7") (pinfunction "OSC_7") (pintype "input+no_connect"))
    )
    (net (code "83") (name "unconnected-(U7-LV-Pad6)") (class "Default")
      (node (ref "U7") (pin "6") (pinfunction "LV_6") (pintype "input+no_connect"))
    )
    (net (code "84") (name "unconnected-(U7-NC-Pad1)") (class "Default")
      (node (ref "U7") (pin "1") (pinfunction "NC_1") (pintype "passive+no_connect"))
    )
    (net (code "85") (name "unconnected-(U7-OSC-Pad7)") (class "Default")
      (node (ref "U7") (pin "7") (pinfunction "OSC_7") (pintype "input+no_connect"))
    )
  )
)
